# UD3_1_Digital_IO.net
KiCad netlist of a schematic drawn in Altium Designer
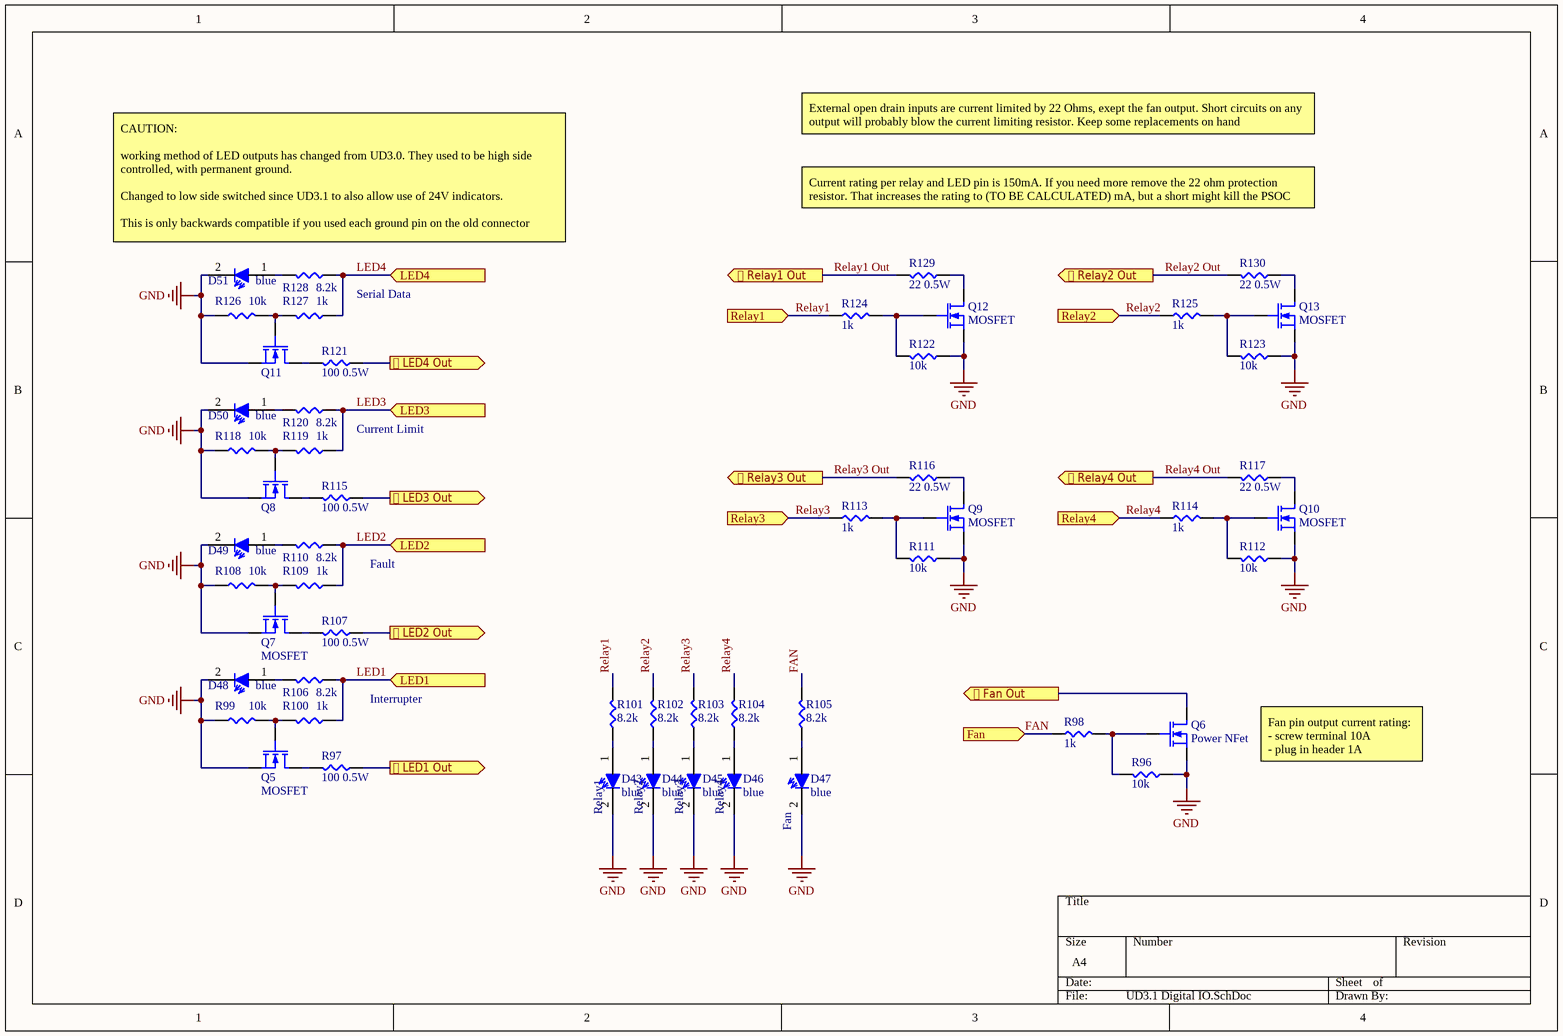
[diagram p0: UD3.1 Digital IO.SchDoc]

(export (version "E")
  (design (tool "Eeschema 10.0.6"))
  (components
    (comp (ref "D43")
      (value "blue")
      (footprint "1206 Reverse Mount")
      (description "Diode, but it lights up")
      (libsource (lib "stdLib") (part "LED"))
    )
    (comp (ref "D44")
      (value "blue")
      (footprint "1206 Reverse Mount")
      (description "Diode, but it lights up")
      (libsource (lib "stdLib") (part "LED"))
    )
    (comp (ref "D45")
      (value "blue")
      (footprint "1206 Reverse Mount")
      (description "Diode, but it lights up")
      (libsource (lib "stdLib") (part "LED"))
    )
    (comp (ref "D46")
      (value "blue")
      (footprint "1206 Reverse Mount")
      (description "Diode, but it lights up")
      (libsource (lib "stdLib") (part "LED"))
    )
    (comp (ref "D47")
      (value "blue")
      (footprint "1206 Reverse Mount")
      (description "Diode, but it lights up")
      (libsource (lib "stdLib") (part "LED"))
    )
    (comp (ref "D48")
      (value "blue")
      (footprint "1206 Reverse Mount")
      (description "Diode, but it lights up")
      (libsource (lib "stdLib") (part "LED"))
    )
    (comp (ref "D49")
      (value "blue")
      (footprint "1206 Reverse Mount")
      (description "Diode, but it lights up")
      (libsource (lib "stdLib") (part "LED"))
    )
    (comp (ref "D50")
      (value "blue")
      (footprint "1206 Reverse Mount")
      (description "Diode, but it lights up")
      (libsource (lib "stdLib") (part "LED"))
    )
    (comp (ref "D51")
      (value "blue")
      (footprint "1206 Reverse Mount")
      (description "Diode, but it lights up")
      (libsource (lib "stdLib") (part "LED"))
    )
    (comp (ref "Q5") (value "MOSFET") (footprint "sot 23") (libsource (lib "stdLib") (part "Mosfet N")))
    (comp (ref "Q6") (value "Power NFet") (footprint "SOIC8") (libsource (lib "stdLib") (part "Mosfet N")))
    (comp (ref "Q7") (value "MOSFET") (footprint "sot 23") (libsource (lib "stdLib") (part "Mosfet N")))
    (comp (ref "Q8") (value "MOSFET") (footprint "sot 23") (libsource (lib "stdLib") (part "Mosfet N")))
    (comp (ref "Q9") (value "MOSFET") (footprint "sot 23") (libsource (lib "stdLib") (part "Mosfet N")))
    (comp (ref "Q10") (value "MOSFET") (footprint "sot 23") (libsource (lib "stdLib") (part "Mosfet N")))
    (comp (ref "Q11") (value "MOSFET") (footprint "sot 23") (libsource (lib "stdLib") (part "Mosfet N")))
    (comp (ref "Q12") (value "MOSFET") (footprint "sot 23") (libsource (lib "stdLib") (part "Mosfet N")))
    (comp (ref "Q13") (value "MOSFET") (footprint "sot 23") (libsource (lib "stdLib") (part "Mosfet N")))
    (comp (ref "R96") (value "10k") (footprint "0603") (libsource (lib "stdLib") (part "Resistor")))
    (comp (ref "R97") (value "100 0.5W") (footprint "1206") (libsource (lib "stdLib") (part "Resistor")))
    (comp (ref "R98") (value "1k") (footprint "0603") (libsource (lib "stdLib") (part "Resistor")))
    (comp (ref "R99") (value "10k") (footprint "0603") (libsource (lib "stdLib") (part "Resistor")))
    (comp (ref "R100") (value "1k") (footprint "0603") (libsource (lib "stdLib") (part "Resistor")))
    (comp (ref "R101") (value "8.2k") (footprint "0603") (libsource (lib "stdLib") (part "Resistor")))
    (comp (ref "R102") (value "8.2k") (footprint "0603") (libsource (lib "stdLib") (part "Resistor")))
    (comp (ref "R103") (value "8.2k") (footprint "0603") (libsource (lib "stdLib") (part "Resistor")))
    (comp (ref "R104") (value "8.2k") (footprint "0603") (libsource (lib "stdLib") (part "Resistor")))
    (comp (ref "R105") (value "8.2k") (footprint "0603") (libsource (lib "stdLib") (part "Resistor")))
    (comp (ref "R106") (value "8.2k") (footprint "0603") (libsource (lib "stdLib") (part "Resistor")))
    (comp (ref "R107") (value "100 0.5W") (footprint "1206") (libsource (lib "stdLib") (part "Resistor")))
    (comp (ref "R108") (value "10k") (footprint "0603") (libsource (lib "stdLib") (part "Resistor")))
    (comp (ref "R109") (value "1k") (footprint "0603") (libsource (lib "stdLib") (part "Resistor")))
    (comp (ref "R110") (value "8.2k") (footprint "0603") (libsource (lib "stdLib") (part "Resistor")))
    (comp (ref "R111") (value "10k") (footprint "0603") (libsource (lib "stdLib") (part "Resistor")))
    (comp (ref "R112") (value "10k") (footprint "0603") (libsource (lib "stdLib") (part "Resistor")))
    (comp (ref "R113") (value "1k") (footprint "0603") (libsource (lib "stdLib") (part "Resistor")))
    (comp (ref "R114") (value "1k") (footprint "0603") (libsource (lib "stdLib") (part "Resistor")))
    (comp (ref "R115") (value "100 0.5W") (footprint "1206") (libsource (lib "stdLib") (part "Resistor")))
    (comp (ref "R116") (value "22 0.5W") (footprint "1206") (libsource (lib "stdLib") (part "Resistor")))
    (comp (ref "R117") (value "22 0.5W") (footprint "1206") (libsource (lib "stdLib") (part "Resistor")))
    (comp (ref "R118") (value "10k") (footprint "0603") (libsource (lib "stdLib") (part "Resistor")))
    (comp (ref "R119") (value "1k") (footprint "0603") (libsource (lib "stdLib") (part "Resistor")))
    (comp (ref "R120") (value "8.2k") (footprint "0603") (libsource (lib "stdLib") (part "Resistor")))
    (comp (ref "R121") (value "100 0.5W") (footprint "1206") (libsource (lib "stdLib") (part "Resistor")))
    (comp (ref "R122") (value "10k") (footprint "0603") (libsource (lib "stdLib") (part "Resistor")))
    (comp (ref "R123") (value "10k") (footprint "0603") (libsource (lib "stdLib") (part "Resistor")))
    (comp (ref "R124") (value "1k") (footprint "0603") (libsource (lib "stdLib") (part "Resistor")))
    (comp (ref "R125") (value "1k") (footprint "0603") (libsource (lib "stdLib") (part "Resistor")))
    (comp (ref "R126") (value "10k") (footprint "0603") (libsource (lib "stdLib") (part "Resistor")))
    (comp (ref "R127") (value "1k") (footprint "0603") (libsource (lib "stdLib") (part "Resistor")))
    (comp (ref "R128") (value "8.2k") (footprint "0603") (libsource (lib "stdLib") (part "Resistor")))
    (comp (ref "R129") (value "22 0.5W") (footprint "1206") (libsource (lib "stdLib") (part "Resistor")))
    (comp (ref "R130") (value "22 0.5W") (footprint "1206") (libsource (lib "stdLib") (part "Resistor")))
  )
  (nets
    (net (code "1") (name "/FAN") (class "Default")
      (node (ref "R105") (pin "1") (pinfunction "1_1") (pintype "passive"))
      (node (ref "R98") (pin "1") (pinfunction "1_1") (pintype "passive"))
    )
    (net (code "2") (name "/LED1") (class "Default")
      (node (ref "R100") (pin "1") (pinfunction "1_1") (pintype "passive"))
      (node (ref "R106") (pin "1") (pinfunction "1_1") (pintype "passive"))
    )
    (net (code "3") (name "/LED2") (class "Default")
      (node (ref "R109") (pin "1") (pinfunction "1_1") (pintype "passive"))
      (node (ref "R110") (pin "1") (pinfunction "1_1") (pintype "passive"))
    )
    (net (code "4") (name "/LED3") (class "Default")
      (node (ref "R119") (pin "1") (pinfunction "1_1") (pintype "passive"))
      (node (ref "R120") (pin "1") (pinfunction "1_1") (pintype "passive"))
    )
    (net (code "5") (name "/LED4") (class "Default")
      (node (ref "R127") (pin "1") (pinfunction "1_1") (pintype "passive"))
      (node (ref "R128") (pin "1") (pinfunction "1_1") (pintype "passive"))
    )
    (net (code "6") (name "/Relay1") (class "Default")
      (node (ref "R101") (pin "1") (pinfunction "1_1") (pintype "passive"))
      (node (ref "R124") (pin "1") (pinfunction "1_1") (pintype "passive"))
    )
    (net (code "7") (name "/Relay1 Out") (class "Default")
      (node (ref "R129") (pin "2") (pinfunction "2_2") (pintype "passive"))
    )
    (net (code "8") (name "/Relay2") (class "Default")
      (node (ref "R102") (pin "1") (pinfunction "1_1") (pintype "passive"))
      (node (ref "R125") (pin "1") (pinfunction "1_1") (pintype "passive"))
    )
    (net (code "9") (name "/Relay2 Out") (class "Default")
      (node (ref "R130") (pin "2") (pinfunction "2_2") (pintype "passive"))
    )
    (net (code "10") (name "/Relay3") (class "Default")
      (node (ref "R103") (pin "1") (pinfunction "1_1") (pintype "passive"))
      (node (ref "R113") (pin "1") (pinfunction "1_1") (pintype "passive"))
    )
    (net (code "11") (name "/Relay3 Out") (class "Default")
      (node (ref "R116") (pin "2") (pinfunction "2_2") (pintype "passive"))
    )
    (net (code "12") (name "/Relay4") (class "Default")
      (node (ref "R104") (pin "1") (pinfunction "1_1") (pintype "passive"))
      (node (ref "R114") (pin "1") (pinfunction "1_1") (pintype "passive"))
    )
    (net (code "13") (name "/Relay4 Out") (class "Default")
      (node (ref "R117") (pin "2") (pinfunction "2_2") (pintype "passive"))
    )
    (net (code "14") (name "/⎐ Fan Out") (class "Default")
      (node (ref "Q6") (pin "D") (pinfunction "D_D") (pintype "passive"))
    )
    (net (code "15") (name "/⎐ LED1 Out") (class "Default")
      (node (ref "R97") (pin "1") (pinfunction "1_1") (pintype "passive"))
    )
    (net (code "16") (name "/⎐ LED2 Out") (class "Default")
      (node (ref "R107") (pin "1") (pinfunction "1_1") (pintype "passive"))
    )
    (net (code "17") (name "/⎐ LED3 Out") (class "Default")
      (node (ref "R115") (pin "1") (pinfunction "1_1") (pintype "passive"))
    )
    (net (code "18") (name "/⎐ LED4 Out") (class "Default")
      (node (ref "R121") (pin "1") (pinfunction "1_1") (pintype "passive"))
    )
    (net (code "19") (name "GND") (class "Default")
      (node (ref "D43") (pin "2") (pintype "passive"))
      (node (ref "D44") (pin "2") (pintype "passive"))
      (node (ref "D45") (pin "2") (pintype "passive"))
      (node (ref "D46") (pin "2") (pintype "passive"))
      (node (ref "D47") (pin "2") (pintype "passive"))
      (node (ref "D48") (pin "2") (pintype "passive"))
      (node (ref "D49") (pin "2") (pintype "passive"))
      (node (ref "D50") (pin "2") (pintype "passive"))
      (node (ref "D51") (pin "2") (pintype "passive"))
      (node (ref "Q10") (pin "S") (pinfunction "S_S") (pintype "passive"))
      (node (ref "Q11") (pin "S") (pinfunction "S_S") (pintype "passive"))
      (node (ref "Q12") (pin "S") (pinfunction "S_S") (pintype "passive"))
      (node (ref "Q13") (pin "S") (pinfunction "S_S") (pintype "passive"))
      (node (ref "Q5") (pin "S") (pinfunction "S_S") (pintype "passive"))
      (node (ref "Q6") (pin "S") (pinfunction "S_S") (pintype "passive"))
      (node (ref "Q7") (pin "S") (pinfunction "S_S") (pintype "passive"))
      (node (ref "Q8") (pin "S") (pinfunction "S_S") (pintype "passive"))
      (node (ref "Q9") (pin "S") (pinfunction "S_S") (pintype "passive"))
      (node (ref "R108") (pin "1") (pinfunction "1_1") (pintype "passive"))
      (node (ref "R111") (pin "1") (pinfunction "1_1") (pintype "passive"))
      (node (ref "R112") (pin "1") (pinfunction "1_1") (pintype "passive"))
      (node (ref "R118") (pin "1") (pinfunction "1_1") (pintype "passive"))
      (node (ref "R122") (pin "1") (pinfunction "1_1") (pintype "passive"))
      (node (ref "R123") (pin "1") (pinfunction "1_1") (pintype "passive"))
      (node (ref "R126") (pin "1") (pinfunction "1_1") (pintype "passive"))
      (node (ref "R96") (pin "1") (pinfunction "1_1") (pintype "passive"))
      (node (ref "R99") (pin "1") (pinfunction "1_1") (pintype "passive"))
    )
    (net (code "20") (name "Net-(D43-Pad1)") (class "Default")
      (node (ref "D43") (pin "1") (pintype "passive"))
      (node (ref "R101") (pin "2") (pinfunction "2_2") (pintype "passive"))
    )
    (net (code "21") (name "Net-(D44-Pad1)") (class "Default")
      (node (ref "D44") (pin "1") (pintype "passive"))
      (node (ref "R102") (pin "2") (pinfunction "2_2") (pintype "passive"))
    )
    (net (code "22") (name "Net-(D45-Pad1)") (class "Default")
      (node (ref "D45") (pin "1") (pintype "passive"))
      (node (ref "R103") (pin "2") (pinfunction "2_2") (pintype "passive"))
    )
    (net (code "23") (name "Net-(D46-Pad1)") (class "Default")
      (node (ref "D46") (pin "1") (pintype "passive"))
      (node (ref "R104") (pin "2") (pinfunction "2_2") (pintype "passive"))
    )
    (net (code "24") (name "Net-(D47-Pad1)") (class "Default")
      (node (ref "D47") (pin "1") (pintype "passive"))
      (node (ref "R105") (pin "2") (pinfunction "2_2") (pintype "passive"))
    )
    (net (code "25") (name "Net-(D48-Pad1)") (class "Default")
      (node (ref "D48") (pin "1") (pintype "passive"))
      (node (ref "R106") (pin "2") (pinfunction "2_2") (pintype "passive"))
    )
    (net (code "26") (name "Net-(D49-Pad1)") (class "Default")
      (node (ref "D49") (pin "1") (pintype "passive"))
      (node (ref "R110") (pin "2") (pinfunction "2_2") (pintype "passive"))
    )
    (net (code "27") (name "Net-(D50-Pad1)") (class "Default")
      (node (ref "D50") (pin "1") (pintype "passive"))
      (node (ref "R120") (pin "2") (pinfunction "2_2") (pintype "passive"))
    )
    (net (code "28") (name "Net-(D51-Pad1)") (class "Default")
      (node (ref "D51") (pin "1") (pintype "passive"))
      (node (ref "R128") (pin "2") (pinfunction "2_2") (pintype "passive"))
    )
    (net (code "29") (name "Net-(Q5-PadD)") (class "Default")
      (node (ref "Q5") (pin "D") (pinfunction "D_D") (pintype "passive"))
      (node (ref "R97") (pin "2") (pinfunction "2_2") (pintype "passive"))
    )
    (net (code "30") (name "Net-(Q5-PadG)") (class "Default")
      (node (ref "Q5") (pin "G") (pinfunction "G_G") (pintype "passive"))
      (node (ref "R100") (pin "2") (pinfunction "2_2") (pintype "passive"))
      (node (ref "R99") (pin "2") (pinfunction "2_2") (pintype "passive"))
    )
    (net (code "31") (name "Net-(Q6-PadG)") (class "Default")
      (node (ref "Q6") (pin "G") (pinfunction "G_G") (pintype "passive"))
      (node (ref "R96") (pin "2") (pinfunction "2_2") (pintype "passive"))
      (node (ref "R98") (pin "2") (pinfunction "2_2") (pintype "passive"))
    )
    (net (code "32") (name "Net-(Q7-PadD)") (class "Default")
      (node (ref "Q7") (pin "D") (pinfunction "D_D") (pintype "passive"))
      (node (ref "R107") (pin "2") (pinfunction "2_2") (pintype "passive"))
    )
    (net (code "33") (name "Net-(Q7-PadG)") (class "Default")
      (node (ref "Q7") (pin "G") (pinfunction "G_G") (pintype "passive"))
      (node (ref "R108") (pin "2") (pinfunction "2_2") (pintype "passive"))
      (node (ref "R109") (pin "2") (pinfunction "2_2") (pintype "passive"))
    )
    (net (code "34") (name "Net-(Q8-PadD)") (class "Default")
      (node (ref "Q8") (pin "D") (pinfunction "D_D") (pintype "passive"))
      (node (ref "R115") (pin "2") (pinfunction "2_2") (pintype "passive"))
    )
    (net (code "35") (name "Net-(Q8-PadG)") (class "Default")
      (node (ref "Q8") (pin "G") (pinfunction "G_G") (pintype "passive"))
      (node (ref "R118") (pin "2") (pinfunction "2_2") (pintype "passive"))
      (node (ref "R119") (pin "2") (pinfunction "2_2") (pintype "passive"))
    )
    (net (code "36") (name "Net-(Q9-PadD)") (class "Default")
      (node (ref "Q9") (pin "D") (pinfunction "D_D") (pintype "passive"))
      (node (ref "R116") (pin "1") (pinfunction "1_1") (pintype "passive"))
    )
    (net (code "37") (name "Net-(Q9-PadG)") (class "Default")
      (node (ref "Q9") (pin "G") (pinfunction "G_G") (pintype "passive"))
      (node (ref "R111") (pin "2") (pinfunction "2_2") (pintype "passive"))
      (node (ref "R113") (pin "2") (pinfunction "2_2") (pintype "passive"))
    )
    (net (code "38") (name "Net-(Q10-PadD)") (class "Default")
      (node (ref "Q10") (pin "D") (pinfunction "D_D") (pintype "passive"))
      (node (ref "R117") (pin "1") (pinfunction "1_1") (pintype "passive"))
    )
    (net (code "39") (name "Net-(Q10-PadG)") (class "Default")
      (node (ref "Q10") (pin "G") (pinfunction "G_G") (pintype "passive"))
      (node (ref "R112") (pin "2") (pinfunction "2_2") (pintype "passive"))
      (node (ref "R114") (pin "2") (pinfunction "2_2") (pintype "passive"))
    )
    (net (code "40") (name "Net-(Q11-PadD)") (class "Default")
      (node (ref "Q11") (pin "D") (pinfunction "D_D") (pintype "passive"))
      (node (ref "R121") (pin "2") (pinfunction "2_2") (pintype "passive"))
    )
    (net (code "41") (name "Net-(Q11-PadG)") (class "Default")
      (node (ref "Q11") (pin "G") (pinfunction "G_G") (pintype "passive"))
      (node (ref "R126") (pin "2") (pinfunction "2_2") (pintype "passive"))
      (node (ref "R127") (pin "2") (pinfunction "2_2") (pintype "passive"))
    )
    (net (code "42") (name "Net-(Q12-PadD)") (class "Default")
      (node (ref "Q12") (pin "D") (pinfunction "D_D") (pintype "passive"))
      (node (ref "R129") (pin "1") (pinfunction "1_1") (pintype "passive"))
    )
    (net (code "43") (name "Net-(Q12-PadG)") (class "Default")
      (node (ref "Q12") (pin "G") (pinfunction "G_G") (pintype "passive"))
      (node (ref "R122") (pin "2") (pinfunction "2_2") (pintype "passive"))
      (node (ref "R124") (pin "2") (pinfunction "2_2") (pintype "passive"))
    )
    (net (code "44") (name "Net-(Q13-PadD)") (class "Default")
      (node (ref "Q13") (pin "D") (pinfunction "D_D") (pintype "passive"))
      (node (ref "R130") (pin "1") (pinfunction "1_1") (pintype "passive"))
    )
    (net (code "45") (name "Net-(Q13-PadG)") (class "Default")
      (node (ref "Q13") (pin "G") (pinfunction "G_G") (pintype "passive"))
      (node (ref "R123") (pin "2") (pinfunction "2_2") (pintype "passive"))
      (node (ref "R125") (pin "2") (pinfunction "2_2") (pintype "passive"))
    )
  )
)
